# 06_-_MP3_Player.net
KiCad netlist of a schematic drawn in Altium Designer
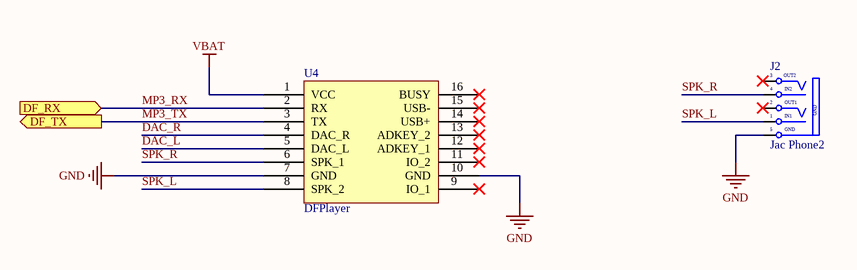
[diagram p0: [06] - MP3 Player.SchDoc]

(export (version "E")
  (design (tool "Eeschema 10.0.6"))
  (components
    (comp (ref "J2")
      (value "Jac Phone2")
      (footprint "JAC_PHONE2")
      (description "Jac Phone Stereo")
      (fields (field (name "CREAT BY") "VanDungEvn@Gmail.com"))
      (libsource (lib "My Library") (part "Jac Phone2"))
    )
    (comp (ref "U4")
      (value "DFPlayer")
      (footprint "DFPlayer")
      (libsource (lib "My Library") (part "DFPlayer"))
    )
  )
  (nets
    (net (code "1") (name "/DAC_L") (class "Default")
      (node (ref "U4") (pin "5") (pinfunction "DAC_L_5") (pintype "passive"))
    )
    (net (code "2") (name "/DAC_R") (class "Default")
      (node (ref "U4") (pin "4") (pinfunction "DAC_R_4") (pintype "passive"))
    )
    (net (code "3") (name "/MP3_RX") (class "Default")
      (node (ref "U4") (pin "2") (pinfunction "RX_2") (pintype "passive"))
    )
    (net (code "4") (name "/MP3_TX") (class "Default")
      (node (ref "U4") (pin "3") (pinfunction "TX_3") (pintype "passive"))
    )
    (net (code "5") (name "/SPK_L") (class "Default")
      (node (ref "J2") (pin "1") (pinfunction "S1_1") (pintype "power_in"))
      (node (ref "U4") (pin "8") (pinfunction "SPK_2_8") (pintype "passive"))
    )
    (net (code "6") (name "/SPK_R") (class "Default")
      (node (ref "J2") (pin "4") (pinfunction "S_4") (pintype "power_in"))
      (node (ref "U4") (pin "6") (pinfunction "SPK_1_6") (pintype "passive"))
    )
    (net (code "7") (name "GND") (class "Default")
      (node (ref "J2") (pin "5") (pinfunction "GND_5") (pintype "passive"))
      (node (ref "U4") (pin "10") (pinfunction "GND_10") (pintype "passive"))
      (node (ref "U4") (pin "7") (pinfunction "GND_7") (pintype "passive"))
    )
    (net (code "8") (name "VBAT") (class "Default")
      (node (ref "U4") (pin "1") (pinfunction "VCC_1") (pintype "passive"))
    )
    (net (code "9") (name "unconnected-(J2-S1-Pad2)") (class "Default")
      (node (ref "J2") (pin "2") (pinfunction "S1_2") (pintype "passive+no_connect"))
    )
    (net (code "10") (name "unconnected-(J2-TN-Pad3)") (class "Default")
      (node (ref "J2") (pin "3") (pinfunction "TN_3") (pintype "passive+no_connect"))
    )
    (net (code "11") (name "unconnected-(U4-ADKEY_1-Pad12)") (class "Default")
      (node (ref "U4") (pin "12") (pinfunction "ADKEY_1_12") (pintype "passive+no_connect"))
    )
    (net (code "12") (name "unconnected-(U4-ADKEY_2-Pad13)") (class "Default")
      (node (ref "U4") (pin "13") (pinfunction "ADKEY_2_13") (pintype "passive+no_connect"))
    )
    (net (code "13") (name "unconnected-(U4-BUSY-Pad16)") (class "Default")
      (node (ref "U4") (pin "16") (pinfunction "BUSY_16") (pintype "passive+no_connect"))
    )
    (net (code "14") (name "unconnected-(U4-IO_1-Pad9)") (class "Default")
      (node (ref "U4") (pin "9") (pinfunction "IO_1_9") (pintype "passive+no_connect"))
    )
    (net (code "15") (name "unconnected-(U4-IO_2-Pad11)") (class "Default")
      (node (ref "U4") (pin "11") (pinfunction "IO_2_11") (pintype "passive+no_connect"))
    )
    (net (code "16") (name "unconnected-(U4-USB+-Pad14)") (class "Default")
      (node (ref "U4") (pin "14") (pinfunction "USB+_14") (pintype "passive+no_connect"))
    )
    (net (code "17") (name "unconnected-(U4-USB--Pad15)") (class "Default")
      (node (ref "U4") (pin "15") (pinfunction "USB-_15") (pintype "passive+no_connect"))
    )
  )
)
